# FMC.net
KiCad netlist of a schematic drawn in Altium Designer
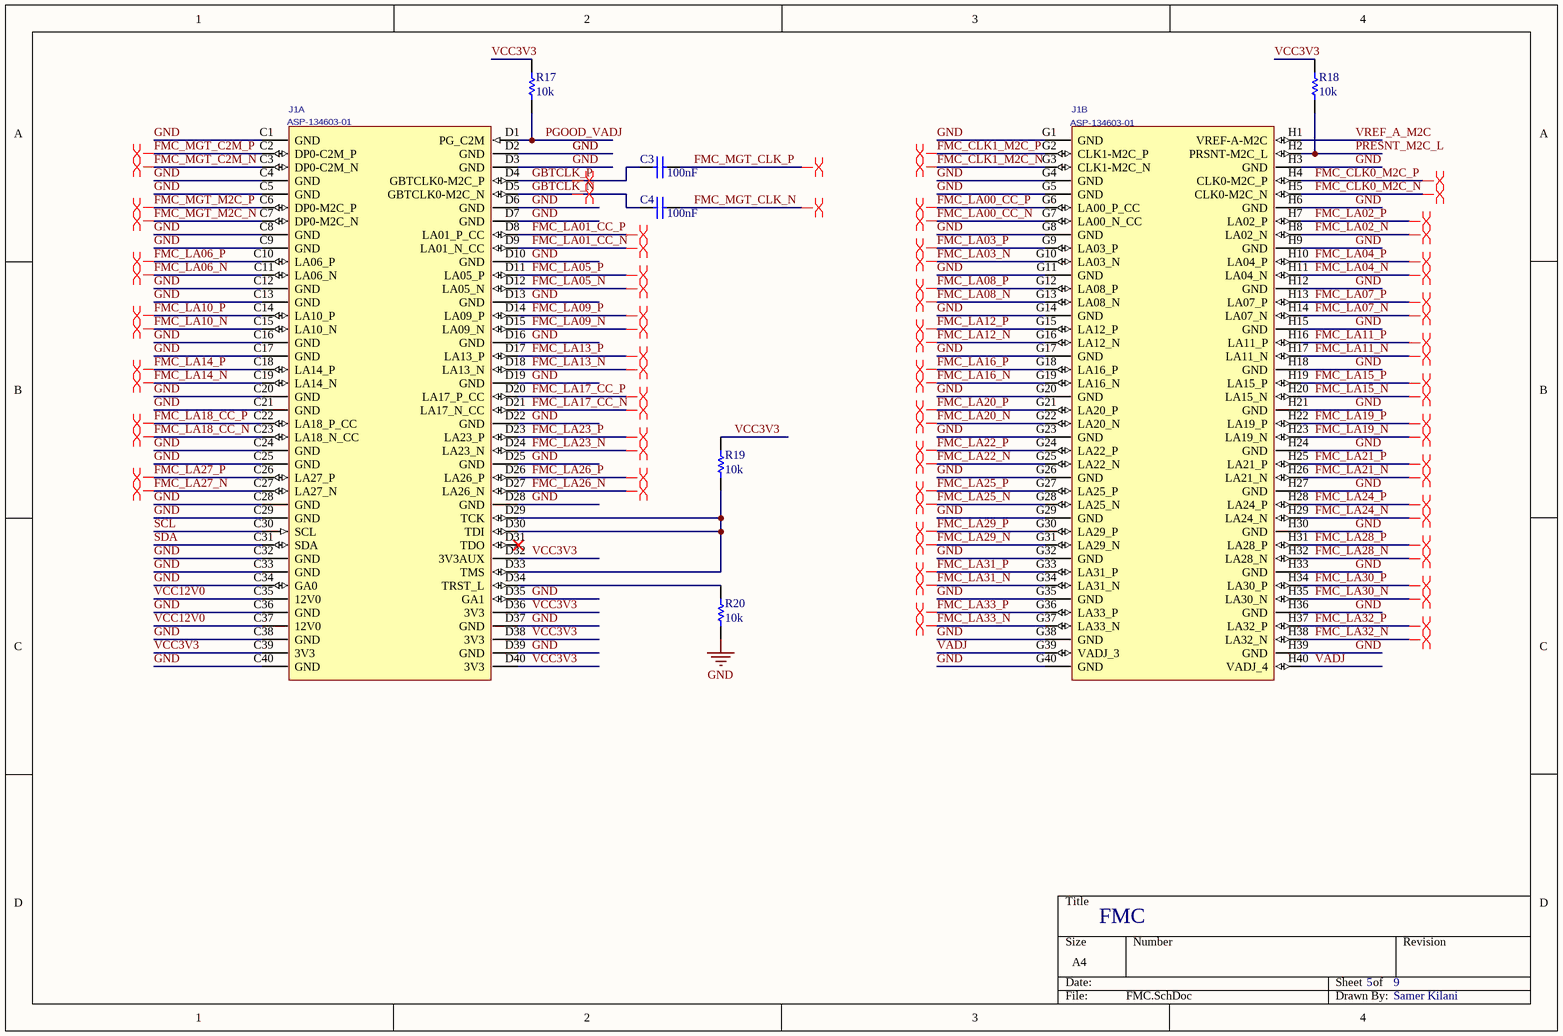
[diagram p0: FMC.SchDoc]

(export (version "E")
  (design (tool "Eeschema 10.0.6"))
  (components
    (comp (ref "C3")
      (value "100nF")
      (footprint "C0402")
      (description "Capacitor")
      (fields (field (name "Comment") "Cap") (field (name "PUBLISHER") "Altium Limited"))
      (libsource (lib "atfclib") (part "Cap"))
    )
    (comp (ref "C4")
      (value "100nF")
      (footprint "C0402")
      (description "Capacitor")
      (fields (field (name "Comment") "Cap") (field (name "PUBLISHER") "Altium Limited"))
      (libsource (lib "atfclib") (part "Cap"))
    )
    (comp (ref "J1")
      (value "ASP-134603-01")
      (footprint "ASP-134603-01")
      (description "0.050\" PITCH SOCKET ARRAY ASSEMBLY.")
      (fields (field (name "MANUFACTURER") "SAMTEC") (field (name "CREATED") "February 27, 2014 - Wedny Xin"))
      (libsource (lib "atfclib") (part "ASP-134603-01"))
    )
    (comp (ref "R17")
      (value "10k")
      (footprint "R0402")
      (description "Resistor")
      (fields (field (name "Comment") "Res"))
      (libsource (lib "atfclib") (part "Res"))
    )
    (comp (ref "R18")
      (value "10k")
      (footprint "R0402")
      (description "Resistor")
      (fields (field (name "Comment") "Res"))
      (libsource (lib "atfclib") (part "Res"))
    )
    (comp (ref "R19")
      (value "10k")
      (footprint "R0402")
      (description "Resistor")
      (fields (field (name "Comment") "Res"))
      (libsource (lib "atfclib") (part "Res"))
    )
    (comp (ref "R20")
      (value "10k")
      (footprint "R0402")
      (description "Resistor")
      (fields (field (name "Comment") "Res"))
      (libsource (lib "atfclib") (part "Res"))
    )
  )
  (nets
    (net (code "1") (name "/FMC_CLK0_M2C_N") (class "Default")
      (node (ref "J1") (pin "H5") (pinfunction "CLK0-M2C_N_H5") (pintype "bidirectional"))
    )
    (net (code "2") (name "/FMC_CLK0_M2C_P") (class "Default")
      (node (ref "J1") (pin "H4") (pinfunction "CLK0-M2C_P_H4") (pintype "bidirectional"))
    )
    (net (code "3") (name "/FMC_CLK1_M2C_N") (class "Default")
      (node (ref "J1") (pin "G3") (pinfunction "CLK1-M2C_N_G3") (pintype "bidirectional"))
    )
    (net (code "4") (name "/FMC_CLK1_M2C_P") (class "Default")
      (node (ref "J1") (pin "G2") (pinfunction "CLK1-M2C_P_G2") (pintype "bidirectional"))
    )
    (net (code "5") (name "/FMC_LA00_CC_N") (class "Default")
      (node (ref "J1") (pin "G7") (pinfunction "LA00_N_CC_G7") (pintype "bidirectional"))
    )
    (net (code "6") (name "/FMC_LA00_CC_P") (class "Default")
      (node (ref "J1") (pin "G6") (pinfunction "LA00_P_CC_G6") (pintype "bidirectional"))
    )
    (net (code "7") (name "/FMC_LA01_CC_N") (class "Default")
      (node (ref "J1") (pin "D9") (pinfunction "LA01_N_CC_D9") (pintype "bidirectional"))
    )
    (net (code "8") (name "/FMC_LA01_CC_P") (class "Default")
      (node (ref "J1") (pin "D8") (pinfunction "LA01_P_CC_D8") (pintype "bidirectional"))
    )
    (net (code "9") (name "/FMC_LA02_N") (class "Default")
      (node (ref "J1") (pin "H8") (pinfunction "LA02_N_H8") (pintype "bidirectional"))
    )
    (net (code "10") (name "/FMC_LA02_P") (class "Default")
      (node (ref "J1") (pin "H7") (pinfunction "LA02_P_H7") (pintype "bidirectional"))
    )
    (net (code "11") (name "/FMC_LA03_N") (class "Default")
      (node (ref "J1") (pin "G10") (pinfunction "LA03_N_G10") (pintype "bidirectional"))
    )
    (net (code "12") (name "/FMC_LA03_P") (class "Default")
      (node (ref "J1") (pin "G9") (pinfunction "LA03_P_G9") (pintype "bidirectional"))
    )
    (net (code "13") (name "/FMC_LA04_N") (class "Default")
      (node (ref "J1") (pin "H11") (pinfunction "LA04_N_H11") (pintype "bidirectional"))
    )
    (net (code "14") (name "/FMC_LA04_P") (class "Default")
      (node (ref "J1") (pin "H10") (pinfunction "LA04_P_H10") (pintype "bidirectional"))
    )
    (net (code "15") (name "/FMC_LA05_N") (class "Default")
      (node (ref "J1") (pin "D12") (pinfunction "LA05_N_D12") (pintype "bidirectional"))
    )
    (net (code "16") (name "/FMC_LA05_P") (class "Default")
      (node (ref "J1") (pin "D11") (pinfunction "LA05_P_D11") (pintype "bidirectional"))
    )
    (net (code "17") (name "/FMC_LA06_N") (class "Default")
      (node (ref "J1") (pin "C11") (pinfunction "LA06_N_C11") (pintype "bidirectional"))
    )
    (net (code "18") (name "/FMC_LA06_P") (class "Default")
      (node (ref "J1") (pin "C10") (pinfunction "LA06_P_C10") (pintype "bidirectional"))
    )
    (net (code "19") (name "/FMC_LA07_N") (class "Default")
      (node (ref "J1") (pin "H14") (pinfunction "LA07_N_H14") (pintype "bidirectional"))
    )
    (net (code "20") (name "/FMC_LA07_P") (class "Default")
      (node (ref "J1") (pin "H13") (pinfunction "LA07_P_H13") (pintype "bidirectional"))
    )
    (net (code "21") (name "/FMC_LA08_N") (class "Default")
      (node (ref "J1") (pin "G13") (pinfunction "LA08_N_G13") (pintype "bidirectional"))
    )
    (net (code "22") (name "/FMC_LA08_P") (class "Default")
      (node (ref "J1") (pin "G12") (pinfunction "LA08_P_G12") (pintype "bidirectional"))
    )
    (net (code "23") (name "/FMC_LA09_N") (class "Default")
      (node (ref "J1") (pin "D15") (pinfunction "LA09_N_D15") (pintype "bidirectional"))
    )
    (net (code "24") (name "/FMC_LA09_P") (class "Default")
      (node (ref "J1") (pin "D14") (pinfunction "LA09_P_D14") (pintype "bidirectional"))
    )
    (net (code "25") (name "/FMC_LA10_N") (class "Default")
      (node (ref "J1") (pin "C15") (pinfunction "LA10_N_C15") (pintype "bidirectional"))
    )
    (net (code "26") (name "/FMC_LA10_P") (class "Default")
      (node (ref "J1") (pin "C14") (pinfunction "LA10_P_C14") (pintype "bidirectional"))
    )
    (net (code "27") (name "/FMC_LA11_N") (class "Default")
      (node (ref "J1") (pin "H17") (pinfunction "LA11_N_H17") (pintype "bidirectional"))
    )
    (net (code "28") (name "/FMC_LA11_P") (class "Default")
      (node (ref "J1") (pin "H16") (pinfunction "LA11_P_H16") (pintype "bidirectional"))
    )
    (net (code "29") (name "/FMC_LA12_N") (class "Default")
      (node (ref "J1") (pin "G16") (pinfunction "LA12_N_G16") (pintype "bidirectional"))
    )
    (net (code "30") (name "/FMC_LA12_P") (class "Default")
      (node (ref "J1") (pin "G15") (pinfunction "LA12_P_G15") (pintype "bidirectional"))
    )
    (net (code "31") (name "/FMC_LA13_N") (class "Default")
      (node (ref "J1") (pin "D18") (pinfunction "LA13_N_D18") (pintype "bidirectional"))
    )
    (net (code "32") (name "/FMC_LA13_P") (class "Default")
      (node (ref "J1") (pin "D17") (pinfunction "LA13_P_D17") (pintype "bidirectional"))
    )
    (net (code "33") (name "/FMC_LA14_N") (class "Default")
      (node (ref "J1") (pin "C19") (pinfunction "LA14_N_C19") (pintype "bidirectional"))
    )
    (net (code "34") (name "/FMC_LA14_P") (class "Default")
      (node (ref "J1") (pin "C18") (pinfunction "LA14_P_C18") (pintype "bidirectional"))
    )
    (net (code "35") (name "/FMC_LA15_N") (class "Default")
      (node (ref "J1") (pin "H20") (pinfunction "LA15_N_H20") (pintype "bidirectional"))
    )
    (net (code "36") (name "/FMC_LA15_P") (class "Default")
      (node (ref "J1") (pin "H19") (pinfunction "LA15_P_H19") (pintype "bidirectional"))
    )
    (net (code "37") (name "/FMC_LA16_N") (class "Default")
      (node (ref "J1") (pin "G19") (pinfunction "LA16_N_G19") (pintype "bidirectional"))
    )
    (net (code "38") (name "/FMC_LA16_P") (class "Default")
      (node (ref "J1") (pin "G18") (pinfunction "LA16_P_G18") (pintype "bidirectional"))
    )
    (net (code "39") (name "/FMC_LA17_CC_N") (class "Default")
      (node (ref "J1") (pin "D21") (pinfunction "LA17_N_CC_D21") (pintype "bidirectional"))
    )
    (net (code "40") (name "/FMC_LA17_CC_P") (class "Default")
      (node (ref "J1") (pin "D20") (pinfunction "LA17_P_CC_D20") (pintype "bidirectional"))
    )
    (net (code "41") (name "/FMC_LA18_CC_N") (class "Default")
      (node (ref "J1") (pin "C23") (pinfunction "LA18_N_CC_C23") (pintype "bidirectional"))
    )
    (net (code "42") (name "/FMC_LA18_CC_P") (class "Default")
      (node (ref "J1") (pin "C22") (pinfunction "LA18_P_CC_C22") (pintype "bidirectional"))
    )
    (net (code "43") (name "/FMC_LA19_N") (class "Default")
      (node (ref "J1") (pin "H23") (pinfunction "LA19_N_H23") (pintype "bidirectional"))
    )
    (net (code "44") (name "/FMC_LA19_P") (class "Default")
      (node (ref "J1") (pin "H22") (pinfunction "LA19_P_H22") (pintype "bidirectional"))
    )
    (net (code "45") (name "/FMC_LA20_N") (class "Default")
      (node (ref "J1") (pin "G22") (pinfunction "LA20_N_G22") (pintype "bidirectional"))
    )
    (net (code "46") (name "/FMC_LA20_P") (class "Default")
      (node (ref "J1") (pin "G21") (pinfunction "LA20_P_G21") (pintype "bidirectional"))
    )
    (net (code "47") (name "/FMC_LA21_N") (class "Default")
      (node (ref "J1") (pin "H26") (pinfunction "LA21_N_H26") (pintype "bidirectional"))
    )
    (net (code "48") (name "/FMC_LA21_P") (class "Default")
      (node (ref "J1") (pin "H25") (pinfunction "LA21_P_H25") (pintype "bidirectional"))
    )
    (net (code "49") (name "/FMC_LA22_N") (class "Default")
      (node (ref "J1") (pin "G25") (pinfunction "LA22_N_G25") (pintype "bidirectional"))
    )
    (net (code "50") (name "/FMC_LA22_P") (class "Default")
      (node (ref "J1") (pin "G24") (pinfunction "LA22_P_G24") (pintype "bidirectional"))
    )
    (net (code "51") (name "/FMC_LA23_N") (class "Default")
      (node (ref "J1") (pin "D24") (pinfunction "LA23_N_D24") (pintype "bidirectional"))
    )
    (net (code "52") (name "/FMC_LA23_P") (class "Default")
      (node (ref "J1") (pin "D23") (pinfunction "LA23_P_D23") (pintype "bidirectional"))
    )
    (net (code "53") (name "/FMC_LA24_N") (class "Default")
      (node (ref "J1") (pin "H29") (pinfunction "LA24_N_H29") (pintype "bidirectional"))
    )
    (net (code "54") (name "/FMC_LA24_P") (class "Default")
      (node (ref "J1") (pin "H28") (pinfunction "LA24_P_H28") (pintype "bidirectional"))
    )
    (net (code "55") (name "/FMC_LA25_N") (class "Default")
      (node (ref "J1") (pin "G28") (pinfunction "LA25_N_G28") (pintype "bidirectional"))
    )
    (net (code "56") (name "/FMC_LA25_P") (class "Default")
      (node (ref "J1") (pin "G27") (pinfunction "LA25_P_G27") (pintype "bidirectional"))
    )
    (net (code "57") (name "/FMC_LA26_N") (class "Default")
      (node (ref "J1") (pin "D27") (pinfunction "LA26_N_D27") (pintype "bidirectional"))
    )
    (net (code "58") (name "/FMC_LA26_P") (class "Default")
      (node (ref "J1") (pin "D26") (pinfunction "LA26_P_D26") (pintype "bidirectional"))
    )
    (net (code "59") (name "/FMC_LA27_N") (class "Default")
      (node (ref "J1") (pin "C27") (pinfunction "LA27_N_C27") (pintype "bidirectional"))
    )
    (net (code "60") (name "/FMC_LA27_P") (class "Default")
      (node (ref "J1") (pin "C26") (pinfunction "LA27_P_C26") (pintype "bidirectional"))
    )
    (net (code "61") (name "/FMC_LA28_N") (class "Default")
      (node (ref "J1") (pin "H32") (pinfunction "LA28_N_H32") (pintype "bidirectional"))
    )
    (net (code "62") (name "/FMC_LA28_P") (class "Default")
      (node (ref "J1") (pin "H31") (pinfunction "LA28_P_H31") (pintype "bidirectional"))
    )
    (net (code "63") (name "/FMC_LA29_N") (class "Default")
      (node (ref "J1") (pin "G31") (pinfunction "LA29_N_G31") (pintype "bidirectional"))
    )
    (net (code "64") (name "/FMC_LA29_P") (class "Default")
      (node (ref "J1") (pin "G30") (pinfunction "LA29_P_G30") (pintype "bidirectional"))
    )
    (net (code "65") (name "/FMC_LA30_N") (class "Default")
      (node (ref "J1") (pin "H35") (pinfunction "LA30_N_H35") (pintype "bidirectional"))
    )
    (net (code "66") (name "/FMC_LA30_P") (class "Default")
      (node (ref "J1") (pin "H34") (pinfunction "LA30_P_H34") (pintype "bidirectional"))
    )
    (net (code "67") (name "/FMC_LA31_N") (class "Default")
      (node (ref "J1") (pin "G34") (pinfunction "LA31_N_G34") (pintype "bidirectional"))
    )
    (net (code "68") (name "/FMC_LA31_P") (class "Default")
      (node (ref "J1") (pin "G33") (pinfunction "LA31_P_G33") (pintype "bidirectional"))
    )
    (net (code "69") (name "/FMC_LA32_N") (class "Default")
      (node (ref "J1") (pin "H38") (pinfunction "LA32_N_H38") (pintype "bidirectional"))
    )
    (net (code "70") (name "/FMC_LA32_P") (class "Default")
      (node (ref "J1") (pin "H37") (pinfunction "LA32_P_H37") (pintype "bidirectional"))
    )
    (net (code "71") (name "/FMC_LA33_N") (class "Default")
      (node (ref "J1") (pin "G37") (pinfunction "LA33_N_G37") (pintype "bidirectional"))
    )
    (net (code "72") (name "/FMC_LA33_P") (class "Default")
      (node (ref "J1") (pin "G36") (pinfunction "LA33_P_G36") (pintype "bidirectional"))
    )
    (net (code "73") (name "/FMC_MGT_C2M_N") (class "Default")
      (node (ref "J1") (pin "C3") (pinfunction "DP0-C2M_N_C3") (pintype "bidirectional"))
    )
    (net (code "74") (name "/FMC_MGT_C2M_P") (class "Default")
      (node (ref "J1") (pin "C2") (pinfunction "DP0-C2M_P_C2") (pintype "bidirectional"))
    )
    (net (code "75") (name "/FMC_MGT_CLK_N") (class "Default")
      (node (ref "C4") (pin "2") (pinfunction "2_2") (pintype "passive"))
    )
    (net (code "76") (name "/FMC_MGT_CLK_P") (class "Default")
      (node (ref "C3") (pin "2") (pinfunction "2_2") (pintype "passive"))
    )
    (net (code "77") (name "/FMC_MGT_M2C_N") (class "Default")
      (node (ref "J1") (pin "C7") (pinfunction "DP0-M2C_N_C7") (pintype "bidirectional"))
    )
    (net (code "78") (name "/FMC_MGT_M2C_P") (class "Default")
      (node (ref "J1") (pin "C6") (pinfunction "DP0-M2C_P_C6") (pintype "bidirectional"))
    )
    (net (code "79") (name "/GBTCLK_N") (class "Default")
      (node (ref "C4") (pin "1") (pinfunction "1_1") (pintype "passive"))
      (node (ref "J1") (pin "D5") (pinfunction "GBTCLK0-M2C_N_D5") (pintype "bidirectional"))
    )
    (net (code "80") (name "/GBTCLK_P") (class "Default")
      (node (ref "C3") (pin "1") (pinfunction "1_1") (pintype "passive"))
      (node (ref "J1") (pin "D4") (pinfunction "GBTCLK0-M2C_P_D4") (pintype "bidirectional"))
    )
    (net (code "81") (name "/PGOOD_VADJ") (class "Default")
      (node (ref "J1") (pin "D1") (pinfunction "PG_C2M_D1") (pintype "input"))
      (node (ref "R17") (pin "1") (pinfunction "1_1") (pintype "passive"))
    )
    (net (code "82") (name "/PRESNT_M2C_L") (class "Default")
      (node (ref "J1") (pin "H2") (pinfunction "PRSNT-M2C_L_H2") (pintype "bidirectional"))
      (node (ref "R18") (pin "1") (pinfunction "1_1") (pintype "passive"))
    )
    (net (code "83") (name "/SCL") (class "Default")
      (node (ref "J1") (pin "C30") (pinfunction "SCL_C30") (pintype "input"))
    )
    (net (code "84") (name "/SDA") (class "Default")
      (node (ref "J1") (pin "C31") (pinfunction "SDA_C31") (pintype "bidirectional"))
    )
    (net (code "85") (name "/VADJ") (class "Default")
      (node (ref "J1") (pin "G39") (pinfunction "VADJ_3_G39") (pintype "bidirectional"))
      (node (ref "J1") (pin "H40") (pinfunction "VADJ_4_H40") (pintype "bidirectional"))
    )
    (net (code "86") (name "/VCC3V3") (class "Default")
      (node (ref "J1") (pin "C39") (pinfunction "3V3_C39") (pintype "passive"))
      (node (ref "J1") (pin "D32") (pinfunction "3V3AUX_D32") (pintype "passive"))
      (node (ref "J1") (pin "D36") (pinfunction "3V3_D36") (pintype "passive"))
      (node (ref "J1") (pin "D38") (pinfunction "3V3_D38") (pintype "passive"))
      (node (ref "J1") (pin "D40") (pinfunction "3V3_D40") (pintype "passive"))
      (node (ref "R17") (pin "2") (pinfunction "2_2") (pintype "passive"))
      (node (ref "R18") (pin "2") (pinfunction "2_2") (pintype "passive"))
      (node (ref "R19") (pin "2") (pinfunction "2_2") (pintype "passive"))
    )
    (net (code "87") (name "/VCC12V0") (class "Default")
      (node (ref "J1") (pin "C35") (pinfunction "12V0_C35") (pintype "passive"))
      (node (ref "J1") (pin "C37") (pinfunction "12V0_C37") (pintype "passive"))
    )
    (net (code "88") (name "/VREF_A_M2C") (class "Default")
      (node (ref "J1") (pin "H1") (pinfunction "VREF-A-M2C_H1") (pintype "bidirectional"))
    )
    (net (code "89") (name "GND") (class "Default")
      (node (ref "J1") (pin "C1") (pinfunction "GND_C1") (pintype "passive"))
      (node (ref "J1") (pin "C12") (pinfunction "GND_C12") (pintype "passive"))
      (node (ref "J1") (pin "C13") (pinfunction "GND_C13") (pintype "passive"))
      (node (ref "J1") (pin "C16") (pinfunction "GND_C16") (pintype "passive"))
      (node (ref "J1") (pin "C17") (pinfunction "GND_C17") (pintype "passive"))
      (node (ref "J1") (pin "C20") (pinfunction "GND_C20") (pintype "passive"))
      (node (ref "J1") (pin "C21") (pinfunction "GND_C21") (pintype "passive"))
      (node (ref "J1") (pin "C24") (pinfunction "GND_C24") (pintype "passive"))
      (node (ref "J1") (pin "C25") (pinfunction "GND_C25") (pintype "passive"))
      (node (ref "J1") (pin "C28") (pinfunction "GND_C28") (pintype "passive"))
      (node (ref "J1") (pin "C29") (pinfunction "GND_C29") (pintype "passive"))
      (node (ref "J1") (pin "C32") (pinfunction "GND_C32") (pintype "passive"))
      (node (ref "J1") (pin "C33") (pinfunction "GND_C33") (pintype "passive"))
      (node (ref "J1") (pin "C34") (pinfunction "GA0_C34") (pintype "bidirectional"))
      (node (ref "J1") (pin "C36") (pinfunction "GND_C36") (pintype "passive"))
      (node (ref "J1") (pin "C38") (pinfunction "GND_C38") (pintype "passive"))
      (node (ref "J1") (pin "C4") (pinfunction "GND_C4") (pintype "passive"))
      (node (ref "J1") (pin "C40") (pinfunction "GND_C40") (pintype "passive"))
      (node (ref "J1") (pin "C5") (pinfunction "GND_C5") (pintype "passive"))
      (node (ref "J1") (pin "C8") (pinfunction "GND_C8") (pintype "passive"))
      (node (ref "J1") (pin "C9") (pinfunction "GND_C9") (pintype "passive"))
      (node (ref "J1") (pin "D10") (pinfunction "GND_D10") (pintype "passive"))
      (node (ref "J1") (pin "D13") (pinfunction "GND_D13") (pintype "passive"))
      (node (ref "J1") (pin "D16") (pinfunction "GND_D16") (pintype "passive"))
      (node (ref "J1") (pin "D19") (pinfunction "GND_D19") (pintype "passive"))
      (node (ref "J1") (pin "D2") (pinfunction "GND_D2") (pintype "passive"))
      (node (ref "J1") (pin "D22") (pinfunction "GND_D22") (pintype "passive"))
      (node (ref "J1") (pin "D25") (pinfunction "GND_D25") (pintype "passive"))
      (node (ref "J1") (pin "D28") (pinfunction "GND_D28") (pintype "passive"))
      (node (ref "J1") (pin "D3") (pinfunction "GND_D3") (pintype "passive"))
      (node (ref "J1") (pin "D35") (pinfunction "GA1_D35") (pintype "bidirectional"))
      (node (ref "J1") (pin "D37") (pinfunction "GND_D37") (pintype "passive"))
      (node (ref "J1") (pin "D39") (pinfunction "GND_D39") (pintype "passive"))
      (node (ref "J1") (pin "D6") (pinfunction "GND_D6") (pintype "passive"))
      (node (ref "J1") (pin "D7") (pinfunction "GND_D7") (pintype "passive"))
      (node (ref "J1") (pin "G1") (pinfunction "GND_G1") (pintype "passive"))
      (node (ref "J1") (pin "G11") (pinfunction "GND_G11") (pintype "passive"))
      (node (ref "J1") (pin "G14") (pinfunction "GND_G14") (pintype "passive"))
      (node (ref "J1") (pin "G17") (pinfunction "GND_G17") (pintype "passive"))
      (node (ref "J1") (pin "G20") (pinfunction "GND_G20") (pintype "passive"))
      (node (ref "J1") (pin "G23") (pinfunction "GND_G23") (pintype "passive"))
      (node (ref "J1") (pin "G26") (pinfunction "GND_G26") (pintype "passive"))
      (node (ref "J1") (pin "G29") (pinfunction "GND_G29") (pintype "passive"))
      (node (ref "J1") (pin "G32") (pinfunction "GND_G32") (pintype "passive"))
      (node (ref "J1") (pin "G35") (pinfunction "GND_G35") (pintype "passive"))
      (node (ref "J1") (pin "G38") (pinfunction "GND_G38") (pintype "passive"))
      (node (ref "J1") (pin "G4") (pinfunction "GND_G4") (pintype "passive"))
      (node (ref "J1") (pin "G40") (pinfunction "GND_G40") (pintype "passive"))
      (node (ref "J1") (pin "G5") (pinfunction "GND_G5") (pintype "passive"))
      (node (ref "J1") (pin "G8") (pinfunction "GND_G8") (pintype "passive"))
      (node (ref "J1") (pin "H12") (pinfunction "GND_H12") (pintype "passive"))
      (node (ref "J1") (pin "H15") (pinfunction "GND_H15") (pintype "passive"))
      (node (ref "J1") (pin "H18") (pinfunction "GND_H18") (pintype "passive"))
      (node (ref "J1") (pin "H21") (pinfunction "GND_H21") (pintype "passive"))
      (node (ref "J1") (pin "H24") (pinfunction "GND_H24") (pintype "passive"))
      (node (ref "J1") (pin "H27") (pinfunction "GND_H27") (pintype "passive"))
      (node (ref "J1") (pin "H3") (pinfunction "GND_H3") (pintype "passive"))
      (node (ref "J1") (pin "H30") (pinfunction "GND_H30") (pintype "passive"))
      (node (ref "J1") (pin "H33") (pinfunction "GND_H33") (pintype "passive"))
      (node (ref "J1") (pin "H36") (pinfunction "GND_H36") (pintype "passive"))
      (node (ref "J1") (pin "H39") (pinfunction "GND_H39") (pintype "passive"))
      (node (ref "J1") (pin "H6") (pinfunction "GND_H6") (pintype "passive"))
      (node (ref "J1") (pin "H9") (pinfunction "GND_H9") (pintype "passive"))
      (node (ref "R20") (pin "1") (pinfunction "1_1") (pintype "passive"))
    )
    (net (code "90") (name "Net-(J1A-TCK)") (class "Default")
      (node (ref "J1") (pin "D29") (pinfunction "TCK_D29") (pintype "bidirectional"))
      (node (ref "J1") (pin "D30") (pinfunction "TDI_D30") (pintype "bidirectional"))
      (node (ref "J1") (pin "D33") (pinfunction "TMS_D33") (pintype "bidirectional"))
      (node (ref "R19") (pin "1") (pinfunction "1_1") (pintype "passive"))
    )
    (net (code "91") (name "Net-(J1A-TRST_L)") (class "Default")
      (node (ref "J1") (pin "D34") (pinfunction "TRST_L_D34") (pintype "bidirectional"))
      (node (ref "R20") (pin "2") (pinfunction "2_2") (pintype "passive"))
    )
    (net (code "92") (name "unconnected-(J1A-TDO-PadD31)") (class "Default")
      (node (ref "J1") (pin "D31") (pinfunction "TDO_D31") (pintype "bidirectional+no_connect"))
    )
  )
)
